# rapidshark-lipo-sensor-mk-3_3.net
KiCad netlist of a schematic drawn in EAGLE
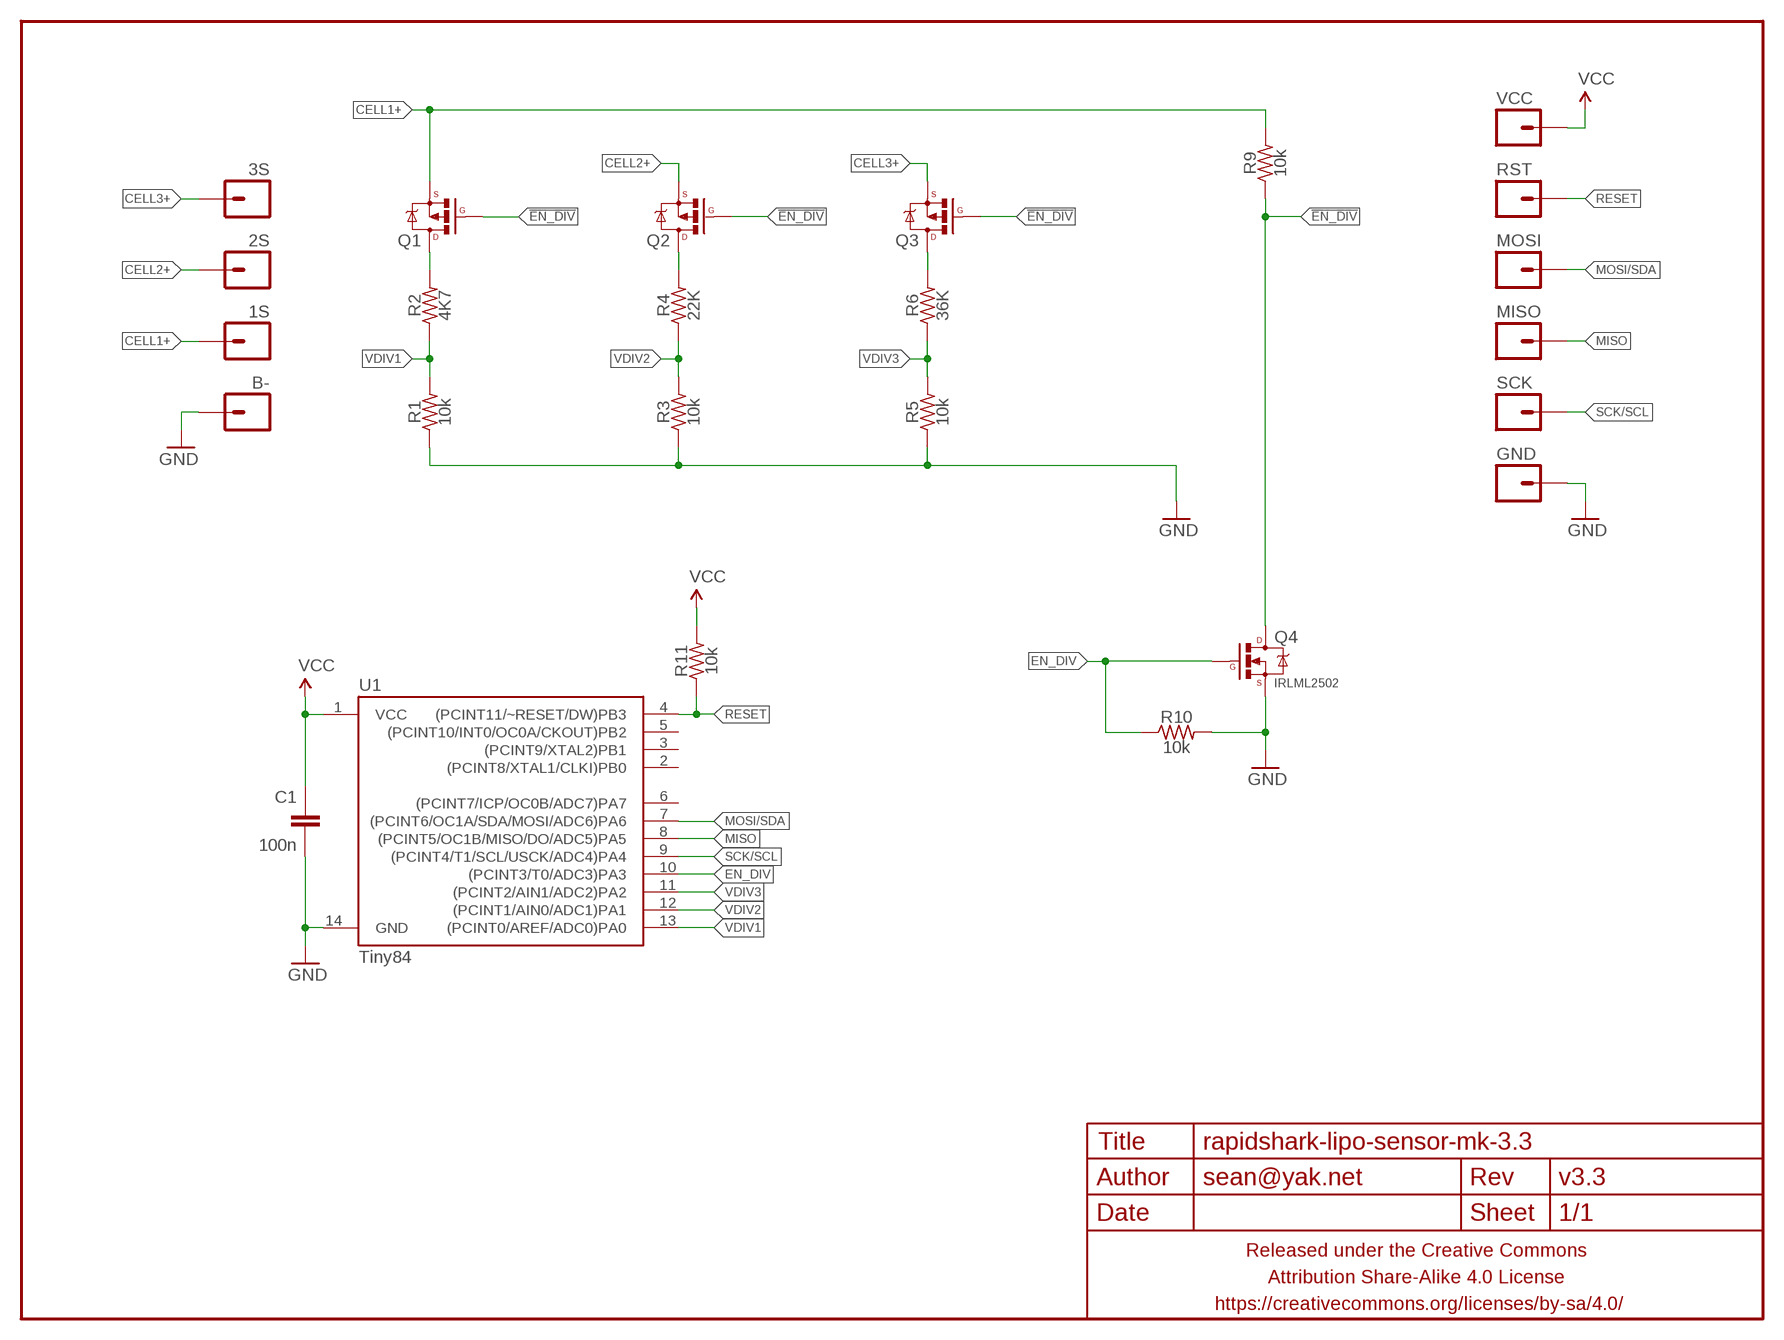
[diagram p0: schematic, sheet 1]

(export (version "E")
  (design (tool "Eeschema 10.0.6"))
  (components
    (comp (ref "1S")
      (value "M01PTH-0.9MM")
      (footprint "eagle-import:1X01-0.9MM")
      (libsource (lib "eagle-import") (part "M01PTH-0.9MM"))
    )
    (comp (ref "2S")
      (value "M01PTH-0.9MM")
      (footprint "eagle-import:1X01-0.9MM")
      (libsource (lib "eagle-import") (part "M01PTH-0.9MM"))
    )
    (comp (ref "3S")
      (value "M01PTH-0.9MM")
      (footprint "eagle-import:1X01-0.9MM")
      (libsource (lib "eagle-import") (part "M01PTH-0.9MM"))
    )
    (comp (ref "B-")
      (value "M01PTH-0.9MM")
      (footprint "eagle-import:1X01-0.9MM")
      (libsource (lib "eagle-import") (part "M01PTH-0.9MM"))
    )
    (comp (ref "C1")
      (value "100n")
      (footprint "eagle-import:C0603-TIGHTER")
      (libsource (lib "eagle-import") (part "CAPACITOR-CERAMICC0603-TIGHTER"))
    )
    (comp (ref "FRAME1")
      (value "FRAME-LETTERNO_PACKAGE")
      (footprint "eagle-import:DUMMY")
      (fields (field (name "DESIGNER") "sean@yak.net") (field (name "VERSION") "v3.3"))
      (libsource (lib "eagle-import") (part "FRAME-LETTERNO_PACKAGE"))
    )
    (comp (ref "GND")
      (value "M01PTH-0.9MM")
      (footprint "eagle-import:1X01-0.9MM")
      (libsource (lib "eagle-import") (part "M01PTH-0.9MM"))
    )
    (comp (ref "MISO")
      (value "M01PTH-0.9MM")
      (footprint "eagle-import:1X01-0.9MM")
      (libsource (lib "eagle-import") (part "M01PTH-0.9MM"))
    )
    (comp (ref "MOSI")
      (value "M01PTH-0.9MM")
      (footprint "eagle-import:1X01-0.9MM")
      (libsource (lib "eagle-import") (part "M01PTH-0.9MM"))
    )
    (comp (ref "Q1")
      (value "MOSFET-PCHANNELSOT-23")
      (footprint "eagle-import:SOT23")
      (libsource (lib "eagle-import") (part "MOSFET-PCHANNELSOT-23"))
    )
    (comp (ref "Q2")
      (value "MOSFET-PCHANNELSOT-23")
      (footprint "eagle-import:SOT23")
      (libsource (lib "eagle-import") (part "MOSFET-PCHANNELSOT-23"))
    )
    (comp (ref "Q3")
      (value "MOSFET-PCHANNELSOT-23")
      (footprint "eagle-import:SOT23")
      (libsource (lib "eagle-import") (part "MOSFET-PCHANNELSOT-23"))
    )
    (comp (ref "Q4")
      (value "IRLML2502")
      (footprint "eagle-import:SOT23")
      (libsource (lib "eagle-import") (part "MOSFET-NCHANNELIRLML2502"))
    )
    (comp (ref "R1")
      (value "10k")
      (footprint "eagle-import:R0603-TIGHTER")
      (libsource (lib "eagle-import") (part "RESISTORR0603-TIGHTER"))
    )
    (comp (ref "R2")
      (value "4K7")
      (footprint "eagle-import:R0603-TIGHTER")
      (libsource (lib "eagle-import") (part "RESISTORR0603-TIGHTER"))
    )
    (comp (ref "R3")
      (value "10k")
      (footprint "eagle-import:R0603-TIGHTER")
      (libsource (lib "eagle-import") (part "RESISTORR0603-TIGHTER"))
    )
    (comp (ref "R4")
      (value "22K")
      (footprint "eagle-import:R0603-TIGHTER")
      (libsource (lib "eagle-import") (part "RESISTORR0603-TIGHTER"))
    )
    (comp (ref "R5")
      (value "10k")
      (footprint "eagle-import:R0603-TIGHTER")
      (libsource (lib "eagle-import") (part "RESISTORR0603-TIGHTER"))
    )
    (comp (ref "R6")
      (value "36K")
      (footprint "eagle-import:R0603-TIGHTER")
      (libsource (lib "eagle-import") (part "RESISTORR0603-TIGHTER"))
    )
    (comp (ref "R9")
      (value "10k")
      (footprint "eagle-import:R0603-TIGHTER")
      (libsource (lib "eagle-import") (part "RESISTORR0603-TIGHTER"))
    )
    (comp (ref "R10")
      (value "10k")
      (footprint "eagle-import:R0603-TIGHTER")
      (libsource (lib "eagle-import") (part "RESISTORR0603-TIGHTER"))
    )
    (comp (ref "R11")
      (value "10k")
      (footprint "eagle-import:R0603-TIGHTER")
      (libsource (lib "eagle-import") (part "RESISTORR0603-TIGHTER"))
    )
    (comp (ref "RST")
      (value "M01PTH-0.9MM")
      (footprint "eagle-import:1X01-0.9MM")
      (libsource (lib "eagle-import") (part "M01PTH-0.9MM"))
    )
    (comp (ref "SCK")
      (value "M01PTH-0.9MM")
      (footprint "eagle-import:1X01-0.9MM")
      (libsource (lib "eagle-import") (part "M01PTH-0.9MM"))
    )
    (comp (ref "U1")
      (value "Tiny84")
      (footprint "eagle-import:SO14")
      (libsource (lib "eagle-import") (part "ATTINY84"))
    )
    (comp (ref "VCC")
      (value "M01PTH-0.9MM")
      (footprint "eagle-import:1X01-0.9MM")
      (libsource (lib "eagle-import") (part "M01PTH-0.9MM"))
    )
  )
  (nets
    (net (code "1") (name "/~{EN_DIV}") (class "Default")
      (node (ref "Q1") (pin "1") (pinfunction "G_1") (pintype "passive"))
      (node (ref "Q2") (pin "1") (pinfunction "G_1") (pintype "passive"))
      (node (ref "Q3") (pin "1") (pinfunction "G_1") (pintype "passive"))
      (node (ref "Q4") (pin "3") (pinfunction "D_3") (pintype "passive"))
      (node (ref "R9") (pin "1") (pinfunction "1_1") (pintype "passive"))
    )
    (net (code "2") (name "CELL1+") (class "Default")
      (node (ref "1S") (pin "1") (pinfunction "1_1") (pintype "passive"))
      (node (ref "Q1") (pin "2") (pinfunction "S_2") (pintype "passive"))
      (node (ref "R9") (pin "2") (pinfunction "2_2") (pintype "passive"))
    )
    (net (code "3") (name "CELL2+") (class "Default")
      (node (ref "2S") (pin "1") (pinfunction "1_1") (pintype "passive"))
      (node (ref "Q2") (pin "2") (pinfunction "S_2") (pintype "passive"))
    )
    (net (code "4") (name "CELL3+") (class "Default")
      (node (ref "3S") (pin "1") (pinfunction "1_1") (pintype "passive"))
      (node (ref "Q3") (pin "2") (pinfunction "S_2") (pintype "passive"))
    )
    (net (code "5") (name "EN_DIV") (class "Default")
      (node (ref "Q4") (pin "1") (pinfunction "G_1") (pintype "passive"))
      (node (ref "R10") (pin "1") (pinfunction "1_1") (pintype "passive"))
      (node (ref "U1") (pin "10") (pinfunction "(PCINT3/T0/ADC3)PA3_10") (pintype "bidirectional"))
    )
    (net (code "6") (name "GND") (class "Default")
      (node (ref "B-") (pin "1") (pinfunction "1_1") (pintype "passive"))
      (node (ref "C1") (pin "2") (pinfunction "2_2") (pintype "passive"))
      (node (ref "GND") (pin "1") (pinfunction "1_1") (pintype "passive"))
      (node (ref "Q4") (pin "2") (pinfunction "S_2") (pintype "passive"))
      (node (ref "R1") (pin "1") (pinfunction "1_1") (pintype "passive"))
      (node (ref "R10") (pin "2") (pinfunction "2_2") (pintype "passive"))
      (node (ref "R3") (pin "1") (pinfunction "1_1") (pintype "passive"))
      (node (ref "R5") (pin "1") (pinfunction "1_1") (pintype "passive"))
      (node (ref "U1") (pin "14") (pinfunction "GND_14") (pintype "bidirectional"))
    )
    (net (code "7") (name "MISO") (class "Default")
      (node (ref "MISO") (pin "1") (pinfunction "1_1") (pintype "passive"))
      (node (ref "U1") (pin "8") (pinfunction "(PCINT5/OC1B/MISO/DO/ADC5)PA5_8") (pintype "bidirectional"))
    )
    (net (code "8") (name "MOSI{slash}SDA") (class "Default")
      (node (ref "MOSI") (pin "1") (pinfunction "1_1") (pintype "passive"))
      (node (ref "U1") (pin "7") (pinfunction "(PCINT6/OC1A/SDA/MOSI/ADC6)PA6_7") (pintype "bidirectional"))
    )
    (net (code "9") (name "Net-(Q1-D)") (class "Default")
      (node (ref "Q1") (pin "3") (pinfunction "D_3") (pintype "passive"))
      (node (ref "R2") (pin "2") (pinfunction "2_2") (pintype "passive"))
    )
    (net (code "10") (name "Net-(Q2-D)") (class "Default")
      (node (ref "Q2") (pin "3") (pinfunction "D_3") (pintype "passive"))
      (node (ref "R4") (pin "2") (pinfunction "2_2") (pintype "passive"))
    )
    (net (code "11") (name "Net-(Q3-D)") (class "Default")
      (node (ref "Q3") (pin "3") (pinfunction "D_3") (pintype "passive"))
      (node (ref "R6") (pin "2") (pinfunction "2_2") (pintype "passive"))
    )
    (net (code "12") (name "RESET") (class "Default")
      (node (ref "R11") (pin "1") (pinfunction "1_1") (pintype "passive"))
      (node (ref "RST") (pin "1") (pinfunction "1_1") (pintype "passive"))
      (node (ref "U1") (pin "4") (pinfunction "(PCINT11/~{RESET/DW})PB3_4") (pintype "bidirectional"))
    )
    (net (code "13") (name "SCK{slash}SCL") (class "Default")
      (node (ref "SCK") (pin "1") (pinfunction "1_1") (pintype "passive"))
      (node (ref "U1") (pin "9") (pinfunction "(PCINT4/T1/SCL/USCK/ADC4)PA4_9") (pintype "bidirectional"))
    )
    (net (code "14") (name "VCC") (class "Default")
      (node (ref "C1") (pin "1") (pinfunction "1_1") (pintype "passive"))
      (node (ref "R11") (pin "2") (pinfunction "2_2") (pintype "passive"))
      (node (ref "U1") (pin "1") (pinfunction "VCC_1") (pintype "bidirectional"))
      (node (ref "VCC") (pin "1") (pinfunction "1_1") (pintype "passive"))
    )
    (net (code "15") (name "VDIV1") (class "Default")
      (node (ref "R1") (pin "2") (pinfunction "2_2") (pintype "passive"))
      (node (ref "R2") (pin "1") (pinfunction "1_1") (pintype "passive"))
      (node (ref "U1") (pin "13") (pinfunction "(PCINT0/AREF/ADC0)PA0_13") (pintype "bidirectional"))
    )
    (net (code "16") (name "VDIV2") (class "Default")
      (node (ref "R3") (pin "2") (pinfunction "2_2") (pintype "passive"))
      (node (ref "R4") (pin "1") (pinfunction "1_1") (pintype "passive"))
      (node (ref "U1") (pin "12") (pinfunction "(PCINT1/AIN0/ADC1)PA1_12") (pintype "bidirectional"))
    )
    (net (code "17") (name "VDIV3") (class "Default")
      (node (ref "R5") (pin "2") (pinfunction "2_2") (pintype "passive"))
      (node (ref "R6") (pin "1") (pinfunction "1_1") (pintype "passive"))
      (node (ref "U1") (pin "11") (pinfunction "(PCINT2/AIN1/ADC2)PA2_11") (pintype "bidirectional"))
    )
    (net (code "18") (name "unconnected-(U1-(PCINT7{slash}ICP{slash}OC0B{slash}ADC7)PA7-Pad6)") (class "Default")
      (node (ref "U1") (pin "6") (pinfunction "(PCINT7/ICP/OC0B/ADC7)PA7_6") (pintype "bidirectional"))
    )
    (net (code "19") (name "unconnected-(U1-(PCINT8{slash}XTAL1{slash}CLKI)PB0-Pad2)") (class "Default")
      (node (ref "U1") (pin "2") (pinfunction "(PCINT8/XTAL1/CLKI)PB0_2") (pintype "bidirectional"))
    )
    (net (code "20") (name "unconnected-(U1-(PCINT9{slash}XTAL2)PB1-Pad3)") (class "Default")
      (node (ref "U1") (pin "3") (pinfunction "(PCINT9/XTAL2)PB1_3") (pintype "bidirectional"))
    )
    (net (code "21") (name "unconnected-(U1-(PCINT10{slash}INT0{slash}OC0A{slash}CKOUT)PB2-Pad5)") (class "Default")
      (node (ref "U1") (pin "5") (pinfunction "(PCINT10/INT0/OC0A/CKOUT)PB2_5") (pintype "bidirectional"))
    )
  )
)
